# Buck_Boost_Converter.net
KiCad netlist of a schematic drawn in Altium Designer
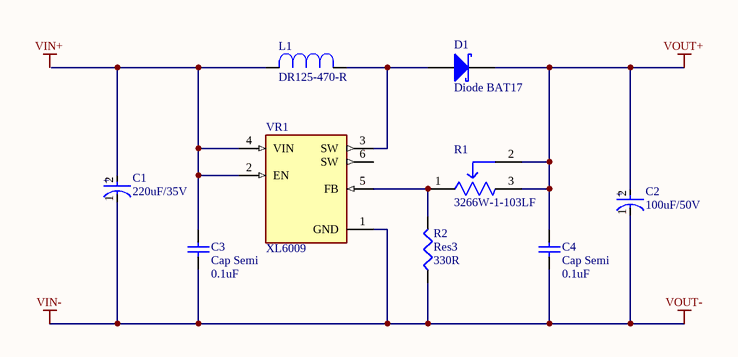
[diagram p0: Buck Boost Converter.SchDoc]

(export (version "E")
  (design (tool "Eeschema 10.0.6"))
  (components
    (comp (ref "C1")
      (value "220uF/35V")
      (footprint "FP-HAG-MFG")
      (libsource (lib "Altium Content Vault") (part "203bc49f2ac43e59fd269a8c329ed05"))
    )
    (comp (ref "C2")
      (value "100uF/50V")
      (footprint "FP-FKF-MFG")
      (description "CAP ALUM 100UF 20% 50V SMD")
      (fields (field (name "VOLTAGE") "50V") (field (name "TOLERANCE") "20%"))
      (libsource (lib "Altium Content Vault") (part "203bc49f2ac43e59fd269a8c329ed05"))
    )
    (comp (ref "C3")
      (value "Cap Semi")
      (footprint "C1206")
      (description "Capacitor (Semiconductor SIM Model)")
      (fields (field (name "ALTIUM_VALUE") "0.1uF") (field (name "PUBLISHER") "Altium Limited"))
      (libsource (lib "Miscellaneous Devices") (part "Cap Semi"))
    )
    (comp (ref "C4")
      (value "Cap Semi")
      (footprint "C1206")
      (description "Capacitor (Semiconductor SIM Model)")
      (fields (field (name "ALTIUM_VALUE") "0.1uF") (field (name "PUBLISHER") "Altium Limited"))
      (libsource (lib "Miscellaneous Devices") (part "Cap Semi"))
    )
    (comp (ref "D1")
      (value "Diode BAT17")
      (footprint "SOT-23_N")
      (description "Silicon RF Schottky Diode for Mixer Applications in the VHF/UHF Range")
      (fields (field (name "PUBLISHER") "Altium Limited"))
      (libsource (lib "Miscellaneous Devices") (part "Diode BAT17"))
    )
    (comp (ref "L1")
      (value "DR125-470-R")
      (footprint "INDM125125X600N")
      (fields (field (name "MF") "Eaton"))
      (libsource (lib "DR125-470-R") (part "DR125-470-R"))
    )
    (comp (ref "R1")
      (value "3266W-1-103LF")
      (footprint "FP-3266W-MFG")
      (description "TRIMMER 10K OHM 0.25W PC PIN TOP")
      (fields
        (field (name "MANUFACTURER") "Bourns")
        (field (name "OCTOPART") "https://octopart.com/3266w-1-103lf-bourns-81445")
      )
      (libsource (lib "Altium Content Vault") (part "5aa38b60e553f01fbee9df648f8b81b"))
    )
    (comp (ref "R2")
      (value "Res3")
      (footprint "J1-0603")
      (description "Resistor")
      (fields (field (name "ALTIUM_VALUE") "330R") (field (name "PUBLISHER") "Altium Limited"))
      (libsource (lib "Miscellaneous Devices") (part "Res3"))
    )
    (comp (ref "VR1")
      (value "XL6009")
      (footprint "DPAK170P1435X465-6N")
      (fields (field (name "MF") "XLSEMI"))
      (libsource (lib "XL6009") (part "XL6009"))
    )
  )
  (nets
    (net (code "1") (name "Net-(C1-A)") (class "Default")
      (node (ref "C1") (pin "2") (pinfunction "A_2") (pintype "passive"))
      (node (ref "C3") (pin "2") (pinfunction "2_2") (pintype "passive"))
      (node (ref "L1") (pin "2") (pinfunction "2_2") (pintype "passive"))
      (node (ref "VR1") (pin "2") (pinfunction "EN_2") (pintype "input"))
      (node (ref "VR1") (pin "4") (pinfunction "VIN_4") (pintype "input"))
    )
    (net (code "2") (name "Net-(D1-A)") (class "Default")
      (node (ref "D1") (pin "1") (pinfunction "A_1") (pintype "passive"))
      (node (ref "L1") (pin "1") (pinfunction "1_1") (pintype "passive"))
      (node (ref "VR1") (pin "3") (pinfunction "SW_3") (pintype "output"))
    )
    (net (code "3") (name "Net-(R1-CCW)") (class "Default")
      (node (ref "R1") (pin "1") (pinfunction "CCW_1") (pintype "passive"))
      (node (ref "R2") (pin "2") (pinfunction "2_2") (pintype "passive"))
      (node (ref "VR1") (pin "5") (pinfunction "FB_5") (pintype "input"))
    )
    (net (code "5") (name "VIN-") (class "Default")
      (node (ref "C1") (pin "1") (pinfunction "C_1") (pintype "passive"))
      (node (ref "C2") (pin "1") (pinfunction "C_1") (pintype "passive"))
      (node (ref "C3") (pin "1") (pinfunction "1_1") (pintype "passive"))
      (node (ref "C4") (pin "1") (pinfunction "1_1") (pintype "passive"))
      (node (ref "R2") (pin "1") (pinfunction "1_1") (pintype "passive"))
      (node (ref "VR1") (pin "1") (pinfunction "GND_1") (pintype "power_in"))
    )
    (net (code "6") (name "VOUT+") (class "Default")
      (node (ref "C2") (pin "2") (pinfunction "A_2") (pintype "passive"))
      (node (ref "C4") (pin "2") (pinfunction "2_2") (pintype "passive"))
      (node (ref "D1") (pin "3") (pinfunction "K_3") (pintype "passive"))
      (node (ref "R1") (pin "2") (pinfunction "WIPER_2") (pintype "passive"))
      (node (ref "R1") (pin "3") (pinfunction "CW_3") (pintype "passive"))
    )
    (net (code "7") (name "unconnected-(VR1-SW-Pad6)") (class "Default")
      (node (ref "VR1") (pin "6") (pinfunction "SW_6") (pintype "output"))
    )
  )
)
